# FPGA_PWR.net
KiCad netlist of a schematic drawn in Altium Designer
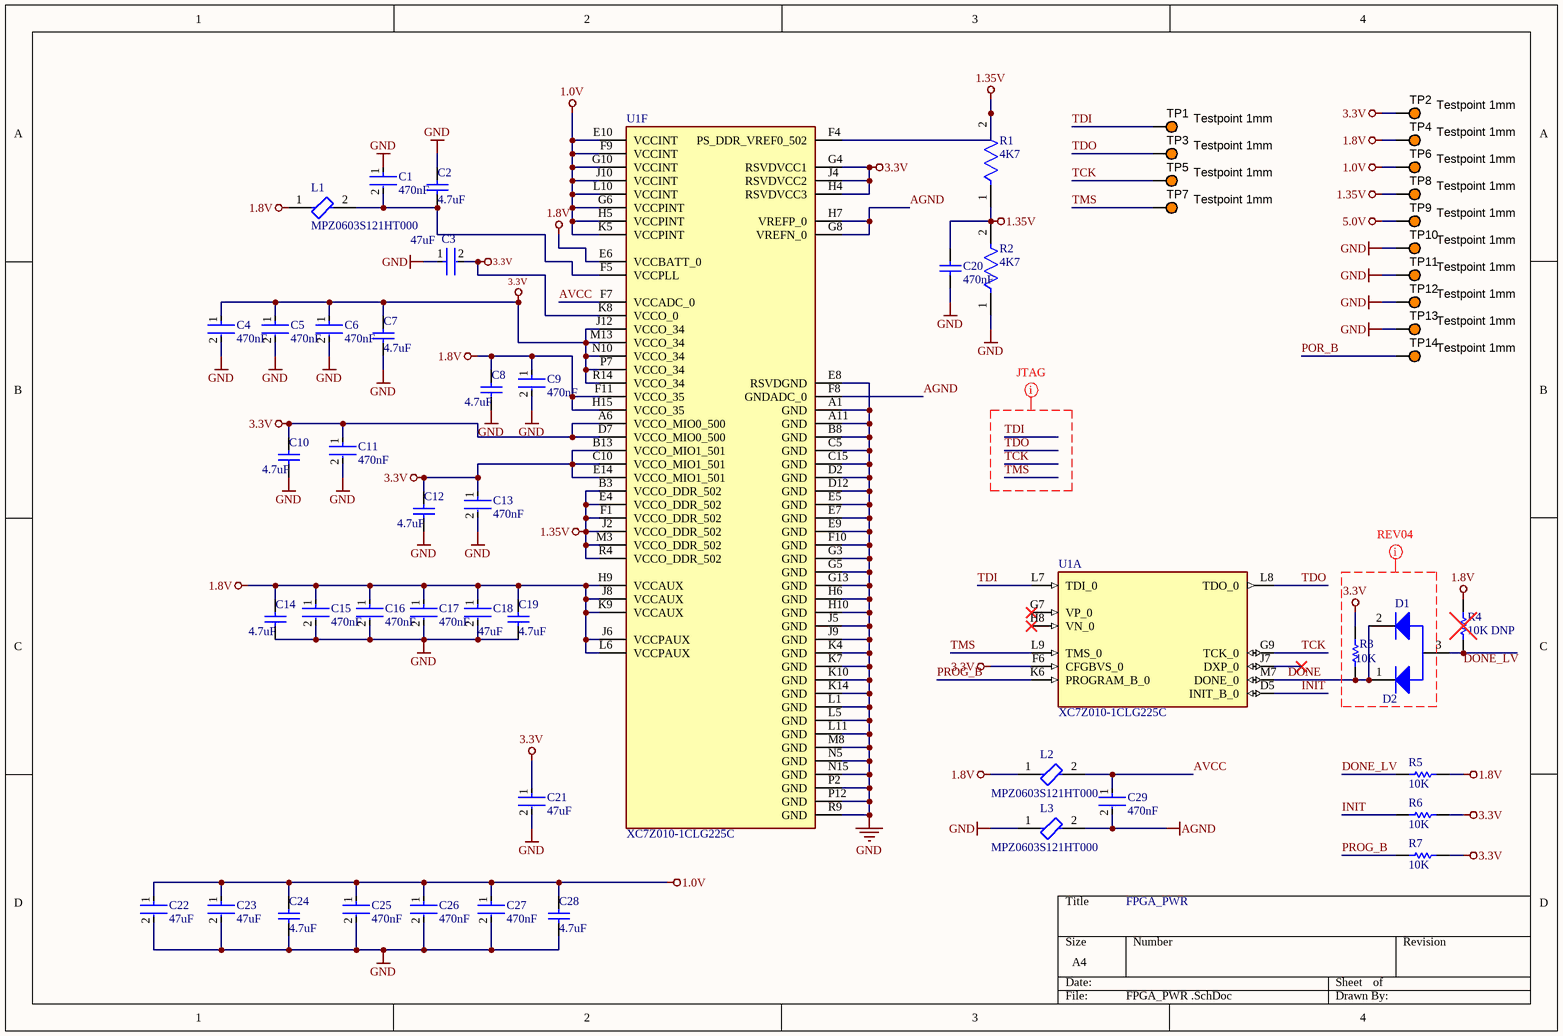
[diagram p0: FPGA_PWR .SchDoc]

(export (version "E")
  (design (tool "Eeschema 10.0.6"))
  (components
    (comp (ref "C1")
      (value "470nF")
      (footprint "FP-0402-L_1_0_0_05-W_0_5-MFG")
      (description "None")
      (fields (field (name "TOLERANCE") "20%"))
      (libsource (lib "Altium Content Vault") (part "b4654b650e69147ec39a6b967a45e02"))
    )
    (comp (ref "C2")
      (value "4.7uF")
      (footprint "CAPC1005X71X25NL10T15")
      (fields
        (field (name "PART NUMBER") "0402ZD475MAT2A")
        (field (name "MANUFACTURER") "AVX Interconnect / Elco")
      )
      (libsource (lib "Altium Content Vault") (part "CAP"))
    )
    (comp (ref "C3")
      (value "47uF")
      (footprint "FP-GRM219-0_2-0_1-IPC_A")
      (description "Chip Multilayer Ceramic Capacitors for General Purpose, 0805, 47uF, X5R, 15%, 20%, 6.3V")
      (fields (field (name "TOLERANCE") "20%"))
      (libsource (lib "Altium Content Vault") (part "02cd4be3c70576c341d710602a673aa"))
    )
    (comp (ref "C4")
      (value "470nF")
      (footprint "FP-0402-L_1_0_0_05-W_0_5-MFG")
      (description "None")
      (fields (field (name "TOLERANCE") "20%"))
      (libsource (lib "Altium Content Vault") (part "b4654b650e69147ec39a6b967a45e02"))
    )
    (comp (ref "C5")
      (value "470nF")
      (footprint "FP-0402-L_1_0_0_05-W_0_5-MFG")
      (description "None")
      (fields (field (name "TOLERANCE") "20%"))
      (libsource (lib "Altium Content Vault") (part "b4654b650e69147ec39a6b967a45e02"))
    )
    (comp (ref "C6")
      (value "470nF")
      (footprint "FP-0402-L_1_0_0_05-W_0_5-MFG")
      (description "None")
      (fields (field (name "TOLERANCE") "20%"))
      (libsource (lib "Altium Content Vault") (part "b4654b650e69147ec39a6b967a45e02"))
    )
    (comp (ref "C7")
      (value "4.7uF")
      (footprint "CAPC1005X71X25NL10T15")
      (fields
        (field (name "PART NUMBER") "0402ZD475MAT2A")
        (field (name "MANUFACTURER") "AVX Interconnect / Elco")
      )
      (libsource (lib "Altium Content Vault") (part "CAP"))
    )
    (comp (ref "C8")
      (value "4.7uF")
      (footprint "CAPC1005X71X25NL10T15")
      (fields
        (field (name "PART NUMBER") "0402ZD475MAT2A")
        (field (name "MANUFACTURER") "AVX Interconnect / Elco")
      )
      (libsource (lib "Altium Content Vault") (part "CAP"))
    )
    (comp (ref "C9")
      (value "470nF")
      (footprint "FP-0402-L_1_0_0_05-W_0_5-MFG")
      (description "None")
      (fields (field (name "TOLERANCE") "20%"))
      (libsource (lib "Altium Content Vault") (part "b4654b650e69147ec39a6b967a45e02"))
    )
    (comp (ref "C10")
      (value "4.7uF")
      (footprint "CAPC1005X71X25NL10T15")
      (fields
        (field (name "PART NUMBER") "0402ZD475MAT2A")
        (field (name "MANUFACTURER") "AVX Interconnect / Elco")
      )
      (libsource (lib "Altium Content Vault") (part "CAP"))
    )
    (comp (ref "C11")
      (value "470nF")
      (footprint "FP-0402-L_1_0_0_05-W_0_5-MFG")
      (description "None")
      (fields (field (name "TOLERANCE") "20%"))
      (libsource (lib "Altium Content Vault") (part "b4654b650e69147ec39a6b967a45e02"))
    )
    (comp (ref "C12")
      (value "4.7uF")
      (footprint "CAPC1005X71X25NL10T15")
      (fields
        (field (name "PART NUMBER") "0402ZD475MAT2A")
        (field (name "MANUFACTURER") "AVX Interconnect / Elco")
      )
      (libsource (lib "Altium Content Vault") (part "CAP"))
    )
    (comp (ref "C13")
      (value "470nF")
      (footprint "FP-0402-L_1_0_0_05-W_0_5-MFG")
      (description "None")
      (fields (field (name "TOLERANCE") "20%"))
      (libsource (lib "Altium Content Vault") (part "b4654b650e69147ec39a6b967a45e02"))
    )
    (comp (ref "C14")
      (value "4.7uF")
      (footprint "CAPC1005X71X25NL10T15")
      (fields
        (field (name "PART NUMBER") "0402ZD475MAT2A")
        (field (name "MANUFACTURER") "AVX Interconnect / Elco")
      )
      (libsource (lib "Altium Content Vault") (part "CAP"))
    )
    (comp (ref "C15")
      (value "470nF")
      (footprint "FP-0402-L_1_0_0_05-W_0_5-MFG")
      (description "None")
      (fields (field (name "TOLERANCE") "20%"))
      (libsource (lib "Altium Content Vault") (part "b4654b650e69147ec39a6b967a45e02"))
    )
    (comp (ref "C16")
      (value "470nF")
      (footprint "FP-0402-L_1_0_0_05-W_0_5-MFG")
      (description "None")
      (fields (field (name "TOLERANCE") "20%"))
      (libsource (lib "Altium Content Vault") (part "b4654b650e69147ec39a6b967a45e02"))
    )
    (comp (ref "C17")
      (value "470nF")
      (footprint "FP-0402-L_1_0_0_05-W_0_5-MFG")
      (description "None")
      (fields (field (name "TOLERANCE") "20%"))
      (libsource (lib "Altium Content Vault") (part "b4654b650e69147ec39a6b967a45e02"))
    )
    (comp (ref "C18")
      (value "47uF")
      (footprint "FP-GRM219-0_2-0_1-IPC_A")
      (description "Chip Multilayer Ceramic Capacitors for General Purpose, 0805, 47uF, X5R, 15%, 20%, 6.3V")
      (fields (field (name "TOLERANCE") "20%"))
      (libsource (lib "Altium Content Vault") (part "02cd4be3c70576c341d710602a673aa"))
    )
    (comp (ref "C19")
      (value "4.7uF")
      (footprint "CAPC1005X71X25NL10T15")
      (fields
        (field (name "PART NUMBER") "0402ZD475MAT2A")
        (field (name "MANUFACTURER") "AVX Interconnect / Elco")
      )
      (libsource (lib "Altium Content Vault") (part "CAP"))
    )
    (comp (ref "C20")
      (value "470nF")
      (footprint "CAPC1005X56X25LL10T15")
      (fields
        (field (name "MANUFACTURER") "AVX Interconnect / Elco")
        (field (name "PART NUMBER") "04026D474KAT2A")
      )
      (libsource (lib "Altium Content Vault") (part "CAP"))
    )
    (comp (ref "C21")
      (value "47uF")
      (footprint "FP-GRM219-0_2-0_1-IPC_A")
      (description "Chip Multilayer Ceramic Capacitors for General Purpose, 0805, 47uF, X5R, 15%, 20%, 6.3V")
      (fields (field (name "TOLERANCE") "20%"))
      (libsource (lib "Altium Content Vault") (part "02cd4be3c70576c341d710602a673aa"))
    )
    (comp (ref "C22")
      (value "47uF")
      (footprint "FP-GRM219-0_2-0_1-IPC_A")
      (description "Chip Multilayer Ceramic Capacitors for General Purpose, 0805, 47uF, X5R, 15%, 20%, 6.3V")
      (fields (field (name "TOLERANCE") "20%"))
      (libsource (lib "Altium Content Vault") (part "02cd4be3c70576c341d710602a673aa"))
    )
    (comp (ref "C23")
      (value "47uF")
      (footprint "FP-GRM219-0_2-0_1-IPC_A")
      (description "Chip Multilayer Ceramic Capacitors for General Purpose, 0805, 47uF, X5R, 15%, 20%, 6.3V")
      (fields (field (name "TOLERANCE") "20%"))
      (libsource (lib "Altium Content Vault") (part "02cd4be3c70576c341d710602a673aa"))
    )
    (comp (ref "C24")
      (value "4.7uF")
      (footprint "CAPC1005X71X25NL10T15")
      (fields
        (field (name "PART NUMBER") "0402ZD475MAT2A")
        (field (name "MANUFACTURER") "AVX Interconnect / Elco")
      )
      (libsource (lib "Altium Content Vault") (part "CAP"))
    )
    (comp (ref "C25")
      (value "470nF")
      (footprint "FP-0402-L_1_0_0_05-W_0_5-MFG")
      (description "None")
      (fields (field (name "TOLERANCE") "20%"))
      (libsource (lib "Altium Content Vault") (part "b4654b650e69147ec39a6b967a45e02"))
    )
    (comp (ref "C26")
      (value "470nF")
      (footprint "FP-0402-L_1_0_0_05-W_0_5-MFG")
      (description "None")
      (fields (field (name "TOLERANCE") "20%"))
      (libsource (lib "Altium Content Vault") (part "b4654b650e69147ec39a6b967a45e02"))
    )
    (comp (ref "C27")
      (value "470nF")
      (footprint "FP-0402-L_1_0_0_05-W_0_5-MFG")
      (description "None")
      (fields (field (name "TOLERANCE") "20%"))
      (libsource (lib "Altium Content Vault") (part "b4654b650e69147ec39a6b967a45e02"))
    )
    (comp (ref "C28")
      (value "4.7uF")
      (footprint "CAPC1005X71X25NL10T15")
      (fields
        (field (name "PART NUMBER") "0402ZD475MAT2A")
        (field (name "MANUFACTURER") "AVX Interconnect / Elco")
      )
      (libsource (lib "Altium Content Vault") (part "CAP"))
    )
    (comp (ref "C29")
      (value "470nF")
      (footprint "FP-0402-L_1_0_0_05-W_0_5-MFG")
      (description "None")
      (fields (field (name "TOLERANCE") "20%"))
      (libsource (lib "Altium Content Vault") (part "b4654b650e69147ec39a6b967a45e02"))
    )
    (comp (ref "D1")
      (value "D2")
      (footprint "ONSC-SOT-323-3-419-04_V")
      (description "Schottky Barrier Diodes, 3-Pin SOT-323, Pb-Free, Tape and Reel")
      (fields (field (name "PARTNUMBER") "BAT54AWT1G") (field (name "MANUFACTURER") "On Semiconductor"))
      (libsource (lib "Altium Content Vault") (part "ONSC-D-K1K2A3-3"))
    )
    (comp (ref "L1")
      (value "MPZ0603S121HT000")
      (footprint "FP-MPZ0603-IPC_C")
      (description "CHIP BEADS FOR GENERAL SIGNAL LI")
      (libsource (lib "Altium Content Vault") (part "5f30dd21d616792df468990f7003faa"))
    )
    (comp (ref "L2")
      (value "MPZ0603S121HT000")
      (footprint "FP-MPZ0603-IPC_C")
      (description "CHIP BEADS FOR GENERAL SIGNAL LI")
      (libsource (lib "Altium Content Vault") (part "5f30dd21d616792df468990f7003faa"))
    )
    (comp (ref "L3")
      (value "MPZ0603S121HT000")
      (footprint "FP-MPZ0603-IPC_C")
      (description "CHIP BEADS FOR GENERAL SIGNAL LI")
      (libsource (lib "Altium Content Vault") (part "5f30dd21d616792df468990f7003faa"))
    )
    (comp (ref "R1")
      (value "4K7")
      (footprint "FP-AC0402-MFG")
      (description "RES 4.7kΩ ±1% 0.063W 0402")
      (libsource (lib "Altium Content Vault") (part "1029c3af85768c4190bb7ad29bc67b5"))
    )
    (comp (ref "R2")
      (value "4K7")
      (footprint "FP-AC0402-MFG")
      (description "RES 4.7kΩ ±1% 0.063W 0402")
      (libsource (lib "Altium Content Vault") (part "1029c3af85768c4190bb7ad29bc67b5"))
    )
    (comp (ref "R3")
      (value "10K")
      (footprint "RESC1005X40X25LL10T10")
      (fields (field (name "MANUFACTURER") "KOA Speer") (field (name "PART NUMBER") "SG73P1ETTP1002F"))
      (libsource (lib "Altium Content Vault") (part "RES"))
    )
    (comp (ref "R4")
      (value "10K DNP")
      (footprint "RESC1005X40X25LL10T10")
      (fields (field (name "MANUFACTURER") "KOA Speer") (field (name "PART NUMBER") "SG73P1ETTP1002F"))
      (libsource (lib "Altium Content Vault") (part "RES"))
    )
    (comp (ref "R5")
      (value "10K")
      (footprint "RESC1005X40X25LL10T10")
      (fields (field (name "MANUFACTURER") "KOA Speer") (field (name "PART NUMBER") "SG73P1ETTP1002F"))
      (libsource (lib "Altium Content Vault") (part "RES"))
    )
    (comp (ref "R6")
      (value "10K")
      (footprint "RESC1005X40X25LL10T10")
      (fields (field (name "MANUFACTURER") "KOA Speer") (field (name "PART NUMBER") "SG73P1ETTP1002F"))
      (libsource (lib "Altium Content Vault") (part "RES"))
    )
    (comp (ref "R7")
      (value "10K")
      (footprint "RESC1005X40X25LL10T10")
      (fields (field (name "MANUFACTURER") "KOA Speer") (field (name "PART NUMBER") "SG73P1ETTP1002F"))
      (libsource (lib "Altium Content Vault") (part "RES"))
    )
    (comp (ref "TP1")
      (value "Testpoint 1mm")
      (footprint "KSTN-5003")
      (description "Test Point, Orange, 1-Pin THD, RoHS")
      (libsource (lib "Altium Content Vault") (part "TESTPOINT_ORANGE"))
    )
    (comp (ref "TP2")
      (value "Testpoint 1mm")
      (footprint "KSTN-5003")
      (description "Test Point, Orange, 1-Pin THD, RoHS")
      (libsource (lib "Altium Content Vault") (part "TESTPOINT_ORANGE"))
    )
    (comp (ref "TP3")
      (value "Testpoint 1mm")
      (footprint "KSTN-5003")
      (description "Test Point, Orange, 1-Pin THD, RoHS")
      (libsource (lib "Altium Content Vault") (part "TESTPOINT_ORANGE"))
    )
    (comp (ref "TP4")
      (value "Testpoint 1mm")
      (footprint "KSTN-5003")
      (description "Test Point, Orange, 1-Pin THD, RoHS")
      (libsource (lib "Altium Content Vault") (part "TESTPOINT_ORANGE"))
    )
    (comp (ref "TP5")
      (value "Testpoint 1mm")
      (footprint "KSTN-5003")
      (description "Test Point, Orange, 1-Pin THD, RoHS")
      (libsource (lib "Altium Content Vault") (part "TESTPOINT_ORANGE"))
    )
    (comp (ref "TP6")
      (value "Testpoint 1mm")
      (footprint "KSTN-5003")
      (description "Test Point, Orange, 1-Pin THD, RoHS")
      (libsource (lib "Altium Content Vault") (part "TESTPOINT_ORANGE"))
    )
    (comp (ref "TP7")
      (value "Testpoint 1mm")
      (footprint "KSTN-5003")
      (description "Test Point, Orange, 1-Pin THD, RoHS")
      (libsource (lib "Altium Content Vault") (part "TESTPOINT_ORANGE"))
    )
    (comp (ref "TP8")
      (value "Testpoint 1mm")
      (footprint "KSTN-5003")
      (description "Test Point, Orange, 1-Pin THD, RoHS")
      (libsource (lib "Altium Content Vault") (part "TESTPOINT_ORANGE"))
    )
    (comp (ref "TP9")
      (value "Testpoint 1mm")
      (footprint "KSTN-5003")
      (description "Test Point, Orange, 1-Pin THD, RoHS")
      (libsource (lib "Altium Content Vault") (part "TESTPOINT_ORANGE"))
    )
    (comp (ref "TP10")
      (value "Testpoint 1mm")
      (footprint "KSTN-5003")
      (description "Test Point, Orange, 1-Pin THD, RoHS")
      (libsource (lib "Altium Content Vault") (part "TESTPOINT_ORANGE"))
    )
    (comp (ref "TP11")
      (value "Testpoint 1mm")
      (footprint "KSTN-5003")
      (description "Test Point, Orange, 1-Pin THD, RoHS")
      (libsource (lib "Altium Content Vault") (part "TESTPOINT_ORANGE"))
    )
    (comp (ref "TP12")
      (value "Testpoint 1mm")
      (footprint "KSTN-5003")
      (description "Test Point, Orange, 1-Pin THD, RoHS")
      (libsource (lib "Altium Content Vault") (part "TESTPOINT_ORANGE"))
    )
    (comp (ref "TP13")
      (value "Testpoint 1mm")
      (footprint "KSTN-5003")
      (description "Test Point, Orange, 1-Pin THD, RoHS")
      (libsource (lib "Altium Content Vault") (part "TESTPOINT_ORANGE"))
    )
    (comp (ref "TP14")
      (value "Testpoint 1mm")
      (footprint "KSTN-5003")
      (description "Test Point, Orange, 1-Pin THD, RoHS")
      (libsource (lib "Altium Content Vault") (part "TESTPOINT_ORANGE"))
    )
    (comp (ref "U1")
      (value "XC7Z010-1CLG225C")
      (footprint "BGA225C80P15X15_1300X1300X150")
      (fields (field (name "MF") "Xilinx Inc.") (field (name "DIGI-KEY_PART_NUMBER") "122-1855-ND"))
      (libsource (lib "XC7Z010-1CLG225C (2)") (part "XC7Z010-1CLG225C"))
    )
  )
  (nets
    (net (code "1") (name "/AVCC") (class "Default")
      (node (ref "C29") (pin "1") (pinfunction "1_1") (pintype "passive"))
      (node (ref "L2") (pin "2") (pinfunction "2_2") (pintype "passive"))
      (node (ref "U1") (pin "F7") (pinfunction "VCCADC_0_F7") (pintype "power_in"))
    )
    (net (code "2") (name "/DONE") (class "Default")
      (node (ref "D1") (pin "1") (pinfunction "K1_1") (pintype "passive"))
      (node (ref "D1") (pin "2") (pinfunction "K2_2") (pintype "passive"))
      (node (ref "R3") (pin "1") (pinfunction "1_1") (pintype "passive"))
      (node (ref "U1") (pin "M7") (pinfunction "DONE_0_M7") (pintype "bidirectional"))
    )
    (net (code "3") (name "/DONE_LV") (class "Default")
      (node (ref "R5") (pin "1") (pinfunction "1_1") (pintype "passive"))
    )
    (net (code "4") (name "/INIT") (class "Default")
      (node (ref "R6") (pin "1") (pinfunction "1_1") (pintype "passive"))
      (node (ref "U1") (pin "D5") (pinfunction "INIT_B_0_D5") (pintype "bidirectional"))
    )
    (net (code "5") (name "/POR_B") (class "Default")
      (node (ref "TP14") (pin "1") (pinfunction "1_1") (pintype "passive"))
    )
    (net (code "6") (name "/PROG_B") (class "Default")
      (node (ref "R7") (pin "1") (pinfunction "1_1") (pintype "passive"))
      (node (ref "U1") (pin "K6") (pinfunction "PROGRAM_B_0_K6") (pintype "input"))
    )
    (net (code "7") (name "/TCK") (class "Default")
      (node (ref "TP5") (pin "1") (pinfunction "1_1") (pintype "passive"))
      (node (ref "U1") (pin "G9") (pinfunction "TCK_0_G9") (pintype "bidirectional"))
    )
    (net (code "8") (name "/TDI") (class "Default")
      (node (ref "TP1") (pin "1") (pinfunction "1_1") (pintype "passive"))
      (node (ref "U1") (pin "L7") (pinfunction "TDI_0_L7") (pintype "input"))
    )
    (net (code "9") (name "/TDO") (class "Default")
      (node (ref "TP3") (pin "1") (pinfunction "1_1") (pintype "passive"))
      (node (ref "U1") (pin "L8") (pinfunction "TDO_0_L8") (pintype "output"))
    )
    (net (code "10") (name "/TMS") (class "Default")
      (node (ref "TP7") (pin "1") (pinfunction "1_1") (pintype "passive"))
      (node (ref "U1") (pin "L9") (pinfunction "TMS_0_L9") (pintype "input"))
    )
    (net (code "11") (name "1.0V") (class "Default")
      (node (ref "C22") (pin "1") (pinfunction "1_1") (pintype "passive"))
      (node (ref "C23") (pin "1") (pinfunction "1_1") (pintype "passive"))
      (node (ref "C24") (pin "2") (pinfunction "2_2") (pintype "passive"))
      (node (ref "C25") (pin "1") (pinfunction "1_1") (pintype "passive"))
      (node (ref "C26") (pin "1") (pinfunction "1_1") (pintype "passive"))
      (node (ref "C27") (pin "1") (pinfunction "1_1") (pintype "passive"))
      (node (ref "C28") (pin "2") (pinfunction "2_2") (pintype "passive"))
      (node (ref "TP6") (pin "1") (pinfunction "1_1") (pintype "passive"))
      (node (ref "U1") (pin "E10") (pinfunction "VCCINT_E10") (pintype "power_in"))
      (node (ref "U1") (pin "F9") (pinfunction "VCCINT_F9") (pintype "power_in"))
      (node (ref "U1") (pin "G10") (pinfunction "VCCINT_G10") (pintype "power_in"))
      (node (ref "U1") (pin "G6") (pinfunction "VCCPINT_G6") (pintype "power_in"))
      (node (ref "U1") (pin "H5") (pinfunction "VCCPINT_H5") (pintype "power_in"))
      (node (ref "U1") (pin "J10") (pinfunction "VCCINT_J10") (pintype "power_in"))
      (node (ref "U1") (pin "K5") (pinfunction "VCCPINT_K5") (pintype "power_in"))
      (node (ref "U1") (pin "L10") (pinfunction "VCCINT_L10") (pintype "power_in"))
    )
    (net (code "12") (name "1.8V") (class "Default")
      (node (ref "C14") (pin "2") (pinfunction "2_2") (pintype "passive"))
      (node (ref "C15") (pin "1") (pinfunction "1_1") (pintype "passive"))
      (node (ref "C16") (pin "1") (pinfunction "1_1") (pintype "passive"))
      (node (ref "C17") (pin "1") (pinfunction "1_1") (pintype "passive"))
      (node (ref "C18") (pin "1") (pinfunction "1_1") (pintype "passive"))
      (node (ref "C19") (pin "2") (pinfunction "2_2") (pintype "passive"))
      (node (ref "C8") (pin "2") (pinfunction "2_2") (pintype "passive"))
      (node (ref "C9") (pin "1") (pinfunction "1_1") (pintype "passive"))
      (node (ref "L1") (pin "1") (pinfunction "1_1") (pintype "passive"))
      (node (ref "L2") (pin "1") (pinfunction "1_1") (pintype "passive"))
      (node (ref "R4") (pin "2") (pinfunction "2_2") (pintype "passive"))
      (node (ref "R5") (pin "2") (pinfunction "2_2") (pintype "passive"))
      (node (ref "TP4") (pin "1") (pinfunction "1_1") (pintype "passive"))
      (node (ref "U1") (pin "E6") (pinfunction "VCCBATT_0_E6") (pintype "power_in"))
      (node (ref "U1") (pin "F11") (pinfunction "VCCO_35_F11") (pintype "power_in"))
      (node (ref "U1") (pin "H15") (pinfunction "VCCO_35_H15") (pintype "power_in"))
      (node (ref "U1") (pin "H9") (pinfunction "VCCAUX_H9") (pintype "power_in"))
      (node (ref "U1") (pin "J6") (pinfunction "VCCPAUX_J6") (pintype "power_in"))
      (node (ref "U1") (pin "J8") (pinfunction "VCCAUX_J8") (pintype "power_in"))
      (node (ref "U1") (pin "K9") (pinfunction "VCCAUX_K9") (pintype "power_in"))
      (node (ref "U1") (pin "L6") (pinfunction "VCCPAUX_L6") (pintype "power_in"))
    )
    (net (code "13") (name "1.35V") (class "Default")
      (node (ref "C20") (pin "2") (pinfunction "2_2") (pintype "passive"))
      (node (ref "R1") (pin "1") (pinfunction "1_1") (pintype "passive"))
      (node (ref "R1") (pin "2") (pinfunction "2_2") (pintype "passive"))
      (node (ref "R2") (pin "2") (pinfunction "2_2") (pintype "passive"))
      (node (ref "TP8") (pin "1") (pinfunction "1_1") (pintype "passive"))
      (node (ref "U1") (pin "B3") (pinfunction "VCCO_DDR_502_B3") (pintype "power_in"))
      (node (ref "U1") (pin "E4") (pinfunction "VCCO_DDR_502_E4") (pintype "power_in"))
      (node (ref "U1") (pin "F1") (pinfunction "VCCO_DDR_502_F1") (pintype "power_in"))
      (node (ref "U1") (pin "F4") (pinfunction "PS_DDR_VREF0_502_F4") (pintype "power_in"))
      (node (ref "U1") (pin "J2") (pinfunction "VCCO_DDR_502_J2") (pintype "power_in"))
      (node (ref "U1") (pin "M3") (pinfunction "VCCO_DDR_502_M3") (pintype "power_in"))
      (node (ref "U1") (pin "R4") (pinfunction "VCCO_DDR_502_R4") (pintype "power_in"))
    )
    (net (code "14") (name "3.3V") (class "Default")
      (node (ref "C10") (pin "2") (pinfunction "2_2") (pintype "passive"))
      (node (ref "C11") (pin "1") (pinfunction "1_1") (pintype "passive"))
      (node (ref "C12") (pin "2") (pinfunction "2_2") (pintype "passive"))
      (node (ref "C13") (pin "1") (pinfunction "1_1") (pintype "passive"))
      (node (ref "C21") (pin "1") (pinfunction "1_1") (pintype "passive"))
      (node (ref "C3") (pin "2") (pinfunction "2_2") (pintype "passive"))
      (node (ref "C4") (pin "1") (pinfunction "1_1") (pintype "passive"))
      (node (ref "C5") (pin "1") (pinfunction "1_1") (pintype "passive"))
      (node (ref "C6") (pin "1") (pinfunction "1_1") (pintype "passive"))
      (node (ref "C7") (pin "2") (pinfunction "2_2") (pintype "passive"))
      (node (ref "R3") (pin "2") (pinfunction "2_2") (pintype "passive"))
      (node (ref "R6") (pin "2") (pinfunction "2_2") (pintype "passive"))
      (node (ref "R7") (pin "2") (pinfunction "2_2") (pintype "passive"))
      (node (ref "TP2") (pin "1") (pinfunction "1_1") (pintype "passive"))
      (node (ref "U1") (pin "A6") (pinfunction "VCCO_MIO0_500_A6") (pintype "power_in"))
      (node (ref "U1") (pin "B13") (pinfunction "VCCO_MIO1_501_B13") (pintype "power_in"))
      (node (ref "U1") (pin "C10") (pinfunction "VCCO_MIO1_501_C10") (pintype "power_in"))
      (node (ref "U1") (pin "D7") (pinfunction "VCCO_MIO0_500_D7") (pintype "power_in"))
      (node (ref "U1") (pin "E14") (pinfunction "VCCO_MIO1_501_E14") (pintype "power_in"))
      (node (ref "U1") (pin "F6") (pinfunction "CFGBVS_0_F6") (pintype "input"))
      (node (ref "U1") (pin "G4") (pinfunction "RSVDVCC1_G4") (pintype "power_in"))
      (node (ref "U1") (pin "H4") (pinfunction "RSVDVCC3_H4") (pintype "power_in"))
      (node (ref "U1") (pin "J12") (pinfunction "VCCO_34_J12") (pintype "power_in"))
      (node (ref "U1") (pin "J4") (pinfunction "RSVDVCC2_J4") (pintype "power_in"))
      (node (ref "U1") (pin "K8") (pinfunction "VCCO_0_K8") (pintype "power_in"))
      (node (ref "U1") (pin "M13") (pinfunction "VCCO_34_M13") (pintype "power_in"))
      (node (ref "U1") (pin "N10") (pinfunction "VCCO_34_N10") (pintype "power_in"))
      (node (ref "U1") (pin "P7") (pinfunction "VCCO_34_P7") (pintype "power_in"))
      (node (ref "U1") (pin "R14") (pinfunction "VCCO_34_R14") (pintype "power_in"))
    )
    (net (code "15") (name "5.0V") (class "Default")
      (node (ref "TP9") (pin "1") (pinfunction "1_1") (pintype "passive"))
    )
    (net (code "16") (name "AGND") (class "Default")
      (node (ref "C29") (pin "2") (pinfunction "2_2") (pintype "passive"))
      (node (ref "L3") (pin "2") (pinfunction "2_2") (pintype "passive"))
      (node (ref "U1") (pin "F8") (pinfunction "GNDADC_0_F8") (pintype "power_in"))
      (node (ref "U1") (pin "G8") (pinfunction "VREFN_0_G8") (pintype "power_in"))
      (node (ref "U1") (pin "H7") (pinfunction "VREFP_0_H7") (pintype "power_in"))
    )
    (net (code "17") (name "GND") (class "Default")
      (node (ref "C1") (pin "1") (pinfunction "1_1") (pintype "passive"))
      (node (ref "C10") (pin "1") (pinfunction "1_1") (pintype "passive"))
      (node (ref "C11") (pin "2") (pinfunction "2_2") (pintype "passive"))
      (node (ref "C12") (pin "1") (pinfunction "1_1") (pintype "passive"))
      (node (ref "C13") (pin "2") (pinfunction "2_2") (pintype "passive"))
      (node (ref "C14") (pin "1") (pinfunction "1_1") (pintype "passive"))
      (node (ref "C15") (pin "2") (pinfunction "2_2") (pintype "passive"))
      (node (ref "C16") (pin "2") (pinfunction "2_2") (pintype "passive"))
      (node (ref "C17") (pin "2") (pinfunction "2_2") (pintype "passive"))
      (node (ref "C18") (pin "2") (pinfunction "2_2") (pintype "passive"))
      (node (ref "C19") (pin "1") (pinfunction "1_1") (pintype "passive"))
      (node (ref "C2") (pin "2") (pinfunction "2_2") (pintype "passive"))
      (node (ref "C20") (pin "1") (pinfunction "1_1") (pintype "passive"))
      (node (ref "C21") (pin "2") (pinfunction "2_2") (pintype "passive"))
      (node (ref "C22") (pin "2") (pinfunction "2_2") (pintype "passive"))
      (node (ref "C23") (pin "2") (pinfunction "2_2") (pintype "passive"))
      (node (ref "C24") (pin "1") (pinfunction "1_1") (pintype "passive"))
      (node (ref "C25") (pin "2") (pinfunction "2_2") (pintype "passive"))
      (node (ref "C26") (pin "2") (pinfunction "2_2") (pintype "passive"))
      (node (ref "C27") (pin "2") (pinfunction "2_2") (pintype "passive"))
      (node (ref "C28") (pin "1") (pinfunction "1_1") (pintype "passive"))
      (node (ref "C3") (pin "1") (pinfunction "1_1") (pintype "passive"))
      (node (ref "C4") (pin "2") (pinfunction "2_2") (pintype "passive"))
      (node (ref "C5") (pin "2") (pinfunction "2_2") (pintype "passive"))
      (node (ref "C6") (pin "2") (pinfunction "2_2") (pintype "passive"))
      (node (ref "C7") (pin "1") (pinfunction "1_1") (pintype "passive"))
      (node (ref "C8") (pin "1") (pinfunction "1_1") (pintype "passive"))
      (node (ref "C9") (pin "2") (pinfunction "2_2") (pintype "passive"))
      (node (ref "L3") (pin "1") (pinfunction "1_1") (pintype "passive"))
      (node (ref "R2") (pin "1") (pinfunction "1_1") (pintype "passive"))
      (node (ref "TP10") (pin "1") (pinfunction "1_1") (pintype "passive"))
      (node (ref "TP11") (pin "1") (pinfunction "1_1") (pintype "passive"))
      (node (ref "TP12") (pin "1") (pinfunction "1_1") (pintype "passive"))
      (node (ref "TP13") (pin "1") (pinfunction "1_1") (pintype "passive"))
      (node (ref "U1") (pin "A1") (pinfunction "GND_A1") (pintype "power_in"))
      (node (ref "U1") (pin "A11") (pinfunction "GND_A11") (pintype "power_in"))
      (node (ref "U1") (pin "B8") (pinfunction "GND_B8") (pintype "power_in"))
      (node (ref "U1") (pin "C15") (pinfunction "GND_C15") (pintype "power_in"))
      (node (ref "U1") (pin "C5") (pinfunction "GND_C5") (pintype "power_in"))
      (node (ref "U1") (pin "D12") (pinfunction "GND_D12") (pintype "power_in"))
      (node (ref "U1") (pin "D2") (pinfunction "GND_D2") (pintype "power_in"))
      (node (ref "U1") (pin "E5") (pinfunction "GND_E5") (pintype "power_in"))
      (node (ref "U1") (pin "E7") (pinfunction "GND_E7") (pintype "power_in"))
      (node (ref "U1") (pin "E8") (pinfunction "RSVDGND_E8") (pintype "power_in"))
      (node (ref "U1") (pin "E9") (pinfunction "GND_E9") (pintype "power_in"))
      (node (ref "U1") (pin "F10") (pinfunction "GND_F10") (pintype "power_in"))
      (node (ref "U1") (pin "G13") (pinfunction "GND_G13") (pintype "power_in"))
      (node (ref "U1") (pin "G3") (pinfunction "GND_G3") (pintype "power_in"))
      (node (ref "U1") (pin "G5") (pinfunction "GND_G5") (pintype "power_in"))
      (node (ref "U1") (pin "H10") (pinfunction "GND_H10") (pintype "power_in"))
      (node (ref "U1") (pin "H6") (pinfunction "GND_H6") (pintype "power_in"))
      (node (ref "U1") (pin "J5") (pinfunction "GND_J5") (pintype "power_in"))
      (node (ref "U1") (pin "J9") (pinfunction "GND_J9") (pintype "power_in"))
      (node (ref "U1") (pin "K10") (pinfunction "GND_K10") (pintype "power_in"))
      (node (ref "U1") (pin "K14") (pinfunction "GND_K14") (pintype "power_in"))
      (node (ref "U1") (pin "K4") (pinfunction "GND_K4") (pintype "power_in"))
      (node (ref "U1") (pin "K7") (pinfunction "GND_K7") (pintype "power_in"))
      (node (ref "U1") (pin "L1") (pinfunction "GND_L1") (pintype "power_in"))
      (node (ref "U1") (pin "L11") (pinfunction "GND_L11") (pintype "power_in"))
      (node (ref "U1") (pin "L5") (pinfunction "GND_L5") (pintype "power_in"))
      (node (ref "U1") (pin "M8") (pinfunction "GND_M8") (pintype "power_in"))
      (node (ref "U1") (pin "N15") (pinfunction "GND_N15") (pintype "power_in"))
      (node (ref "U1") (pin "N5") (pinfunction "GND_N5") (pintype "power_in"))
      (node (ref "U1") (pin "P12") (pinfunction "GND_P12") (pintype "power_in"))
      (node (ref "U1") (pin "P2") (pinfunction "GND_P2") (pintype "power_in"))
      (node (ref "U1") (pin "R9") (pinfunction "GND_R9") (pintype "power_in"))
    )
    (net (code "18") (name "Net-(D1-A)") (class "Default")
      (node (ref "D1") (pin "3") (pinfunction "A_3") (pintype "passive"))
      (node (ref "R4") (pin "1") (pinfunction "1_1") (pintype "passive"))
    )
    (net (code "19") (name "Net-(U1F-VCCPLL)") (class "Default")
      (node (ref "C1") (pin "2") (pinfunction "2_2") (pintype "passive"))
      (node (ref "C2") (pin "1") (pinfunction "1_1") (pintype "passive"))
      (node (ref "L1") (pin "2") (pinfunction "2_2") (pintype "passive"))
      (node (ref "U1") (pin "F5") (pinfunction "VCCPLL_F5") (pintype "power_in"))
    )
    (net (code "20") (name "unconnected-(U1A-DXP_0-PadJ7)") (class "Default")
      (node (ref "U1") (pin "J7") (pinfunction "DXP_0_J7") (pintype "bidirectional+no_connect"))
    )
    (net (code "21") (name "unconnected-(U1A-VN_0-PadH8)") (class "Default")
      (node (ref "U1") (pin "H8") (pinfunction "VN_0_H8") (pintype "input+no_connect"))
    )
    (net (code "22") (name "unconnected-(U1A-VP_0-PadG7)") (class "Default")
      (node (ref "U1") (pin "G7") (pinfunction "VP_0_G7") (pintype "input+no_connect"))
    )
  )
)
